# schematicsv2.net
KiCad netlist of a schematic drawn in EAGLE
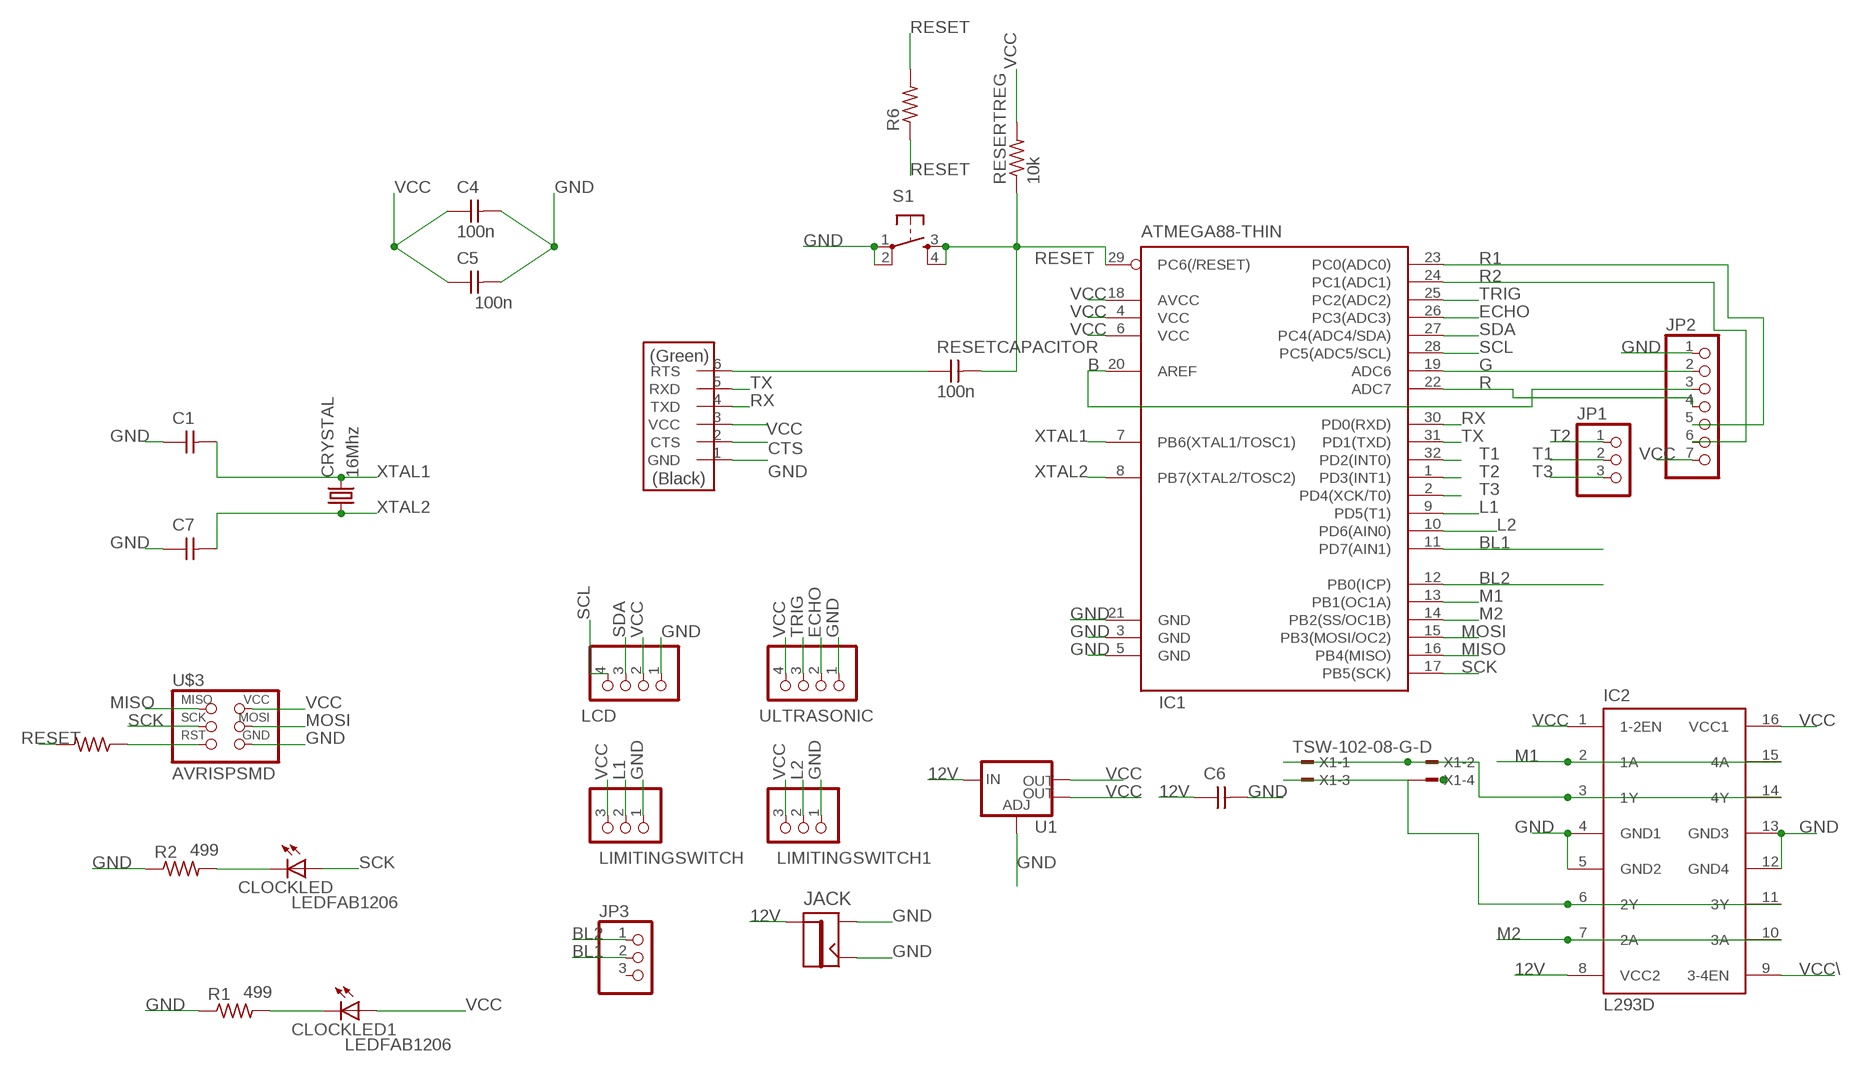
[diagram p0: schematic, sheet 1]

(export (version "E")
  (design (tool "Eeschema 10.0.6"))
  (components
    (comp (ref "C1")
      (value "CAP-UNPOLARIZEDFAB")
      (footprint "eagle-import:C1206FAB")
      (libsource (lib "eagle-import") (part "CAP-UNPOLARIZEDFAB"))
    )
    (comp (ref "C4")
      (value "100n")
      (footprint "eagle-import:C1206FAB")
      (libsource (lib "eagle-import") (part "CAP-UNPOLARIZEDFAB"))
    )
    (comp (ref "C5")
      (value "100n")
      (footprint "eagle-import:C1206FAB")
      (libsource (lib "eagle-import") (part "CAP-UNPOLARIZEDFAB"))
    )
    (comp (ref "C6")
      (value "CAP-UNPOLARIZEDFAB")
      (footprint "eagle-import:C1206FAB")
      (libsource (lib "eagle-import") (part "CAP-UNPOLARIZEDFAB"))
    )
    (comp (ref "C7")
      (value "CAP-UNPOLARIZEDFAB")
      (footprint "eagle-import:C1206FAB")
      (libsource (lib "eagle-import") (part "CAP-UNPOLARIZEDFAB"))
    )
    (comp (ref "CLOCKLED")
      (value "LEDFAB1206")
      (footprint "eagle-import:LED1206FAB")
      (libsource (lib "eagle-import") (part "LEDFAB1206"))
    )
    (comp (ref "CLOCKLED1")
      (value "LEDFAB1206")
      (footprint "eagle-import:LED1206FAB")
      (libsource (lib "eagle-import") (part "LEDFAB1206"))
    )
    (comp (ref "CRYSTAL")
      (value "16Mhz")
      (footprint "eagle-import:CSM-7X-DU")
      (libsource (lib "eagle-import") (part "CSM-7X-DU"))
    )
    (comp (ref "IC1")
      (value "ATMEGA88-THIN")
      (footprint "eagle-import:TQFP32-08THIN")
      (libsource (lib "eagle-import") (part "ATMEGA88-THIN"))
    )
    (comp (ref "IC2")
      (value "L293D")
      (footprint "eagle-import:DIL16")
      (libsource (lib "eagle-import") (part "L293D"))
    )
    (comp (ref "JACK")
      (value "JACK2.1MM")
      (footprint "eagle-import:JACK_2.1MM")
      (libsource (lib "eagle-import") (part "JACK2.1MM"))
    )
    (comp (ref "JP1")
      (value "PINHD-1X31X03_SMT")
      (footprint "eagle-import:1X03_SMT")
      (libsource (lib "eagle-import") (part "PINHD-1X31X03_SMT"))
    )
    (comp (ref "JP2")
      (value "PINHD-1X71X07_SMT")
      (footprint "eagle-import:1X07_SMT")
      (libsource (lib "eagle-import") (part "PINHD-1X71X07_SMT"))
    )
    (comp (ref "JP3")
      (value "PINHD-1X31X03_SMT")
      (footprint "eagle-import:1X03_SMT")
      (libsource (lib "eagle-import") (part "PINHD-1X31X03_SMT"))
    )
    (comp (ref "LCD")
      (value "PINHD-1X41X04_SMT")
      (footprint "eagle-import:1X04_SMT")
      (libsource (lib "eagle-import") (part "PINHD-1X41X04_SMT"))
    )
    (comp (ref "LIMITINGSWITCH")
      (value "PINHD-1X31X03_SMT")
      (footprint "eagle-import:1X03_SMT")
      (libsource (lib "eagle-import") (part "PINHD-1X31X03_SMT"))
    )
    (comp (ref "LIMITINGSWITCH1")
      (value "PINHD-1X31X03_SMT")
      (footprint "eagle-import:1X03_SMT")
      (libsource (lib "eagle-import") (part "PINHD-1X31X03_SMT"))
    )
    (comp (ref "R1")
      (value "499")
      (footprint "eagle-import:R1206FAB")
      (libsource (lib "eagle-import") (part "RES-US1206FAB"))
    )
    (comp (ref "R2")
      (value "499")
      (footprint "eagle-import:R1206FAB")
      (libsource (lib "eagle-import") (part "RES-US1206FAB"))
    )
    (comp (ref "R4")
      (value "1000")
      (footprint "eagle-import:R1206FAB")
      (libsource (lib "eagle-import") (part "RES-US1206FAB"))
    )
    (comp (ref "R6")
      (value "1000")
      (footprint "eagle-import:R1206FAB")
      (libsource (lib "eagle-import") (part "RES-US1206FAB"))
    )
    (comp (ref "RESERTREG")
      (value "10k")
      (footprint "eagle-import:R1206FAB")
      (libsource (lib "eagle-import") (part "RES-US1206FAB"))
    )
    (comp (ref "RESETCAPACITOR")
      (value "100n")
      (footprint "eagle-import:C1206FAB")
      (libsource (lib "eagle-import") (part "CAP-UNPOLARIZEDFAB"))
    )
    (comp (ref "S1")
      (value "6MM_SWITCH6MM_SWITCH")
      (footprint "eagle-import:6MM_SWITCH")
      (libsource (lib "eagle-import") (part "6MM_SWITCH6MM_SWITCH"))
    )
    (comp (ref "U$2")
      (value "FTDI-SMD-HEADER")
      (footprint "eagle-import:1X06SMD")
      (libsource (lib "eagle-import") (part "FTDI-SMD-HEADER"))
    )
    (comp (ref "U$3")
      (value "AVRISPSMD")
      (footprint "eagle-import:2X03SMD")
      (libsource (lib "eagle-import") (part "AVRISPSMD"))
    )
    (comp (ref "U1")
      (value "V_REG_LM1117SOT223")
      (footprint "eagle-import:SOT223")
      (libsource (lib "eagle-import") (part "V_REG_LM1117SOT223"))
    )
    (comp (ref "ULTRASONIC")
      (value "PINHD-1X41X04_SMT")
      (footprint "eagle-import:1X04_SMT")
      (libsource (lib "eagle-import") (part "PINHD-1X41X04_SMT"))
    )
    (comp (ref "X1")
      (value "TSW-102-08-G-D")
      (footprint "eagle-import:TSW-102-XX-G-D")
      (fields (field (name "MF") "Samtec Inc.") (field (name "MPN") "TSW-102-07-G-D"))
      (libsource (lib "eagle-import") (part "TSW-102--G-D08"))
    )
  )
  (nets
    (net (code "1") (name "/12V") (class "Default")
      (node (ref "C6") (pin "1") (pinfunction "1_1") (pintype "passive"))
      (node (ref "IC2") (pin "8") (pinfunction "VCC2_8") (pintype "power_in"))
      (node (ref "JACK") (pin "PIN") (pinfunction "PIN_PIN") (pintype "bidirectional"))
      (node (ref "U1") (pin "3") (pinfunction "IN_3") (pintype "input"))
    )
    (net (code "2") (name "/B") (class "Default")
      (node (ref "IC1") (pin "20") (pinfunction "AREF_20") (pintype "passive"))
      (node (ref "JP2") (pin "3") (pinfunction "3_3") (pintype "passive"))
    )
    (net (code "3") (name "/BL1") (class "Default")
      (node (ref "IC1") (pin "11") (pinfunction "PD7(AIN1)_11") (pintype "bidirectional"))
      (node (ref "JP3") (pin "2") (pinfunction "2_2") (pintype "passive"))
    )
    (net (code "4") (name "/BL2") (class "Default")
      (node (ref "IC1") (pin "12") (pinfunction "PB0(ICP)_12") (pintype "bidirectional"))
      (node (ref "JP3") (pin "1") (pinfunction "1_1") (pintype "passive"))
    )
    (net (code "5") (name "/CTS") (class "Default")
      (node (ref "U$2") (pin "2") (pinfunction "CTS_2") (pintype "bidirectional"))
    )
    (net (code "6") (name "/ECHO") (class "Default")
      (node (ref "IC1") (pin "26") (pinfunction "PC3(ADC3)_26") (pintype "bidirectional"))
      (node (ref "ULTRASONIC") (pin "2") (pinfunction "2_2") (pintype "passive"))
    )
    (net (code "7") (name "/G") (class "Default")
      (node (ref "IC1") (pin "19") (pinfunction "ADC6_19") (pintype "bidirectional"))
      (node (ref "JP2") (pin "2") (pinfunction "2_2") (pintype "passive"))
    )
    (net (code "8") (name "/GND") (class "Default")
      (node (ref "C1") (pin "1") (pinfunction "1_1") (pintype "passive"))
      (node (ref "C4") (pin "2") (pinfunction "2_2") (pintype "passive"))
      (node (ref "C5") (pin "2") (pinfunction "2_2") (pintype "passive"))
      (node (ref "C6") (pin "2") (pinfunction "2_2") (pintype "passive"))
      (node (ref "C7") (pin "1") (pinfunction "1_1") (pintype "passive"))
      (node (ref "IC1") (pin "21") (pinfunction "GND_21") (pintype "power_in"))
      (node (ref "IC1") (pin "3") (pinfunction "GND_3") (pintype "power_in"))
      (node (ref "IC1") (pin "5") (pinfunction "GND_5") (pintype "power_in"))
      (node (ref "IC2") (pin "12") (pinfunction "GND4_12") (pintype "power_in"))
      (node (ref "IC2") (pin "13") (pinfunction "GND3_13") (pintype "power_in"))
      (node (ref "IC2") (pin "4") (pinfunction "GND1_4") (pintype "power_in"))
      (node (ref "IC2") (pin "5") (pinfunction "GND2_5") (pintype "power_in"))
      (node (ref "JACK") (pin "CONTACT") (pinfunction "CONTACT_CONTACT") (pintype "bidirectional"))
      (node (ref "JACK") (pin "SHUNT") (pinfunction "SHUNT_SHUNT") (pintype "bidirectional"))
      (node (ref "JP2") (pin "1") (pinfunction "1_1") (pintype "passive"))
      (node (ref "LCD") (pin "1") (pinfunction "1_1") (pintype "passive"))
      (node (ref "LIMITINGSWITCH") (pin "1") (pinfunction "1_1") (pintype "passive"))
      (node (ref "LIMITINGSWITCH1") (pin "1") (pinfunction "1_1") (pintype "passive"))
      (node (ref "R1") (pin "1") (pinfunction "1_1") (pintype "passive"))
      (node (ref "R2") (pin "1") (pinfunction "1_1") (pintype "passive"))
      (node (ref "S1") (pin "1") (pinfunction "P_1") (pintype "passive"))
      (node (ref "S1") (pin "2") (pinfunction "P1_2") (pintype "passive"))
      (node (ref "U$2") (pin "1") (pinfunction "GND_1") (pintype "bidirectional"))
      (node (ref "U$3") (pin "6") (pinfunction "GND_6") (pintype "passive"))
      (node (ref "U1") (pin "1") (pinfunction "ADJ_1") (pintype "input"))
      (node (ref "ULTRASONIC") (pin "1") (pinfunction "1_1") (pintype "passive"))
    )
    (net (code "9") (name "/L1") (class "Default")
      (node (ref "IC1") (pin "9") (pinfunction "PD5(T1)_9") (pintype "bidirectional"))
      (node (ref "LIMITINGSWITCH") (pin "2") (pinfunction "2_2") (pintype "passive"))
    )
    (net (code "10") (name "/L2") (class "Default")
      (node (ref "IC1") (pin "10") (pinfunction "PD6(AIN0)_10") (pintype "bidirectional"))
      (node (ref "LIMITINGSWITCH1") (pin "2") (pinfunction "2_2") (pintype "passive"))
    )
    (net (code "11") (name "/M1") (class "Default")
      (node (ref "IC1") (pin "13") (pinfunction "PB1(OC1A)_13") (pintype "bidirectional"))
      (node (ref "IC2") (pin "15") (pinfunction "4A_15") (pintype "input"))
      (node (ref "IC2") (pin "2") (pinfunction "1A_2") (pintype "input"))
    )
    (net (code "12") (name "/M2") (class "Default")
      (node (ref "IC1") (pin "14") (pinfunction "PB2(SS/OC1B)_14") (pintype "bidirectional"))
      (node (ref "IC2") (pin "10") (pinfunction "3A_10") (pintype "input"))
      (node (ref "IC2") (pin "7") (pinfunction "2A_7") (pintype "input"))
    )
    (net (code "13") (name "/MISO") (class "Default")
      (node (ref "IC1") (pin "16") (pinfunction "PB4(MISO)_16") (pintype "bidirectional"))
      (node (ref "U$3") (pin "1") (pinfunction "MISO_1") (pintype "passive"))
    )
    (net (code "14") (name "/MOSI") (class "Default")
      (node (ref "IC1") (pin "15") (pinfunction "PB3(MOSI/OC2)_15") (pintype "bidirectional"))
      (node (ref "U$3") (pin "4") (pinfunction "MOSI_4") (pintype "passive"))
    )
    (net (code "15") (name "/R") (class "Default")
      (node (ref "IC1") (pin "22") (pinfunction "ADC7_22") (pintype "bidirectional"))
      (node (ref "JP2") (pin "4") (pinfunction "4_4") (pintype "passive"))
    )
    (net (code "16") (name "/R1") (class "Default")
      (node (ref "IC1") (pin "23") (pinfunction "PC0(ADC0)_23") (pintype "bidirectional"))
      (node (ref "JP2") (pin "5") (pinfunction "5_5") (pintype "passive"))
    )
    (net (code "17") (name "/R2") (class "Default")
      (node (ref "IC1") (pin "24") (pinfunction "PC1(ADC1)_24") (pintype "bidirectional"))
      (node (ref "JP2") (pin "6") (pinfunction "6_6") (pintype "passive"))
    )
    (net (code "18") (name "/RESET") (class "Default")
      (node (ref "IC1") (pin "29") (pinfunction "PC6(/RESET)_29") (pintype "bidirectional"))
      (node (ref "R4") (pin "2") (pinfunction "2_2") (pintype "passive"))
      (node (ref "R6") (pin "1") (pinfunction "1_1") (pintype "passive"))
      (node (ref "R6") (pin "2") (pinfunction "2_2") (pintype "passive"))
      (node (ref "RESERTREG") (pin "1") (pinfunction "1_1") (pintype "passive"))
      (node (ref "RESETCAPACITOR") (pin "2") (pinfunction "2_2") (pintype "passive"))
      (node (ref "S1") (pin "3") (pinfunction "S_3") (pintype "passive"))
      (node (ref "S1") (pin "4") (pinfunction "S1_4") (pintype "passive"))
    )
    (net (code "19") (name "/RX") (class "Default")
      (node (ref "IC1") (pin "30") (pinfunction "PD0(RXD)_30") (pintype "bidirectional"))
      (node (ref "U$2") (pin "4") (pinfunction "TXD_4") (pintype "bidirectional"))
    )
    (net (code "20") (name "/SCK") (class "Default")
      (node (ref "CLOCKLED") (pin "1") (pinfunction "A_1") (pintype "passive"))
      (node (ref "IC1") (pin "17") (pinfunction "PB5(SCK)_17") (pintype "bidirectional"))
      (node (ref "U$3") (pin "3") (pinfunction "SCK_3") (pintype "passive"))
    )
    (net (code "21") (name "/SCL") (class "Default")
      (node (ref "IC1") (pin "28") (pinfunction "PC5(ADC5/SCL)_28") (pintype "bidirectional"))
      (node (ref "LCD") (pin "4") (pinfunction "4_4") (pintype "passive"))
    )
    (net (code "22") (name "/SDA") (class "Default")
      (node (ref "IC1") (pin "27") (pinfunction "PC4(ADC4/SDA)_27") (pintype "bidirectional"))
      (node (ref "LCD") (pin "3") (pinfunction "3_3") (pintype "passive"))
    )
    (net (code "23") (name "/T1") (class "Default")
      (node (ref "IC1") (pin "32") (pinfunction "PD2(INT0)_32") (pintype "bidirectional"))
      (node (ref "JP1") (pin "2") (pinfunction "2_2") (pintype "passive"))
    )
    (net (code "24") (name "/T2") (class "Default")
      (node (ref "IC1") (pin "1") (pinfunction "PD3(INT1)_1") (pintype "bidirectional"))
      (node (ref "JP1") (pin "1") (pinfunction "1_1") (pintype "passive"))
    )
    (net (code "25") (name "/T3") (class "Default")
      (node (ref "IC1") (pin "2") (pinfunction "PD4(XCK/T0)_2") (pintype "bidirectional"))
      (node (ref "JP1") (pin "3") (pinfunction "3_3") (pintype "passive"))
    )
    (net (code "26") (name "/TRIG") (class "Default")
      (node (ref "IC1") (pin "25") (pinfunction "PC2(ADC2)_25") (pintype "bidirectional"))
      (node (ref "ULTRASONIC") (pin "3") (pinfunction "3_3") (pintype "passive"))
    )
    (net (code "27") (name "/TX") (class "Default")
      (node (ref "IC1") (pin "31") (pinfunction "PD1(TXD)_31") (pintype "bidirectional"))
      (node (ref "U$2") (pin "5") (pinfunction "RXD_5") (pintype "bidirectional"))
    )
    (net (code "28") (name "/VCC") (class "Default")
      (node (ref "C4") (pin "1") (pinfunction "1_1") (pintype "passive"))
      (node (ref "C5") (pin "1") (pinfunction "1_1") (pintype "passive"))
      (node (ref "CLOCKLED1") (pin "1") (pinfunction "A_1") (pintype "passive"))
      (node (ref "IC1") (pin "18") (pinfunction "AVCC_18") (pintype "power_in"))
      (node (ref "IC1") (pin "4") (pinfunction "VCC_4") (pintype "power_in"))
      (node (ref "IC1") (pin "6") (pinfunction "VCC_6") (pintype "power_in"))
      (node (ref "IC2") (pin "1") (pinfunction "1-2EN_1") (pintype "input"))
      (node (ref "IC2") (pin "16") (pinfunction "VCC1_16") (pintype "power_in"))
      (node (ref "JP2") (pin "7") (pinfunction "7_7") (pintype "passive"))
      (node (ref "LCD") (pin "2") (pinfunction "2_2") (pintype "passive"))
      (node (ref "LIMITINGSWITCH") (pin "3") (pinfunction "3_3") (pintype "passive"))
      (node (ref "LIMITINGSWITCH1") (pin "3") (pinfunction "3_3") (pintype "passive"))
      (node (ref "RESERTREG") (pin "2") (pinfunction "2_2") (pintype "passive"))
      (node (ref "U$2") (pin "3") (pinfunction "VCC_3") (pintype "bidirectional"))
      (node (ref "U$3") (pin "2") (pinfunction "VCC_2") (pintype "passive"))
      (node (ref "U1") (pin "2") (pinfunction "OUT_2") (pintype "output"))
      (node (ref "U1") (pin "4") (pinfunction "OUT_4") (pintype "output"))
      (node (ref "ULTRASONIC") (pin "4") (pinfunction "4_4") (pintype "passive"))
    )
    (net (code "29") (name "/VCC\\") (class "Default")
      (node (ref "IC2") (pin "9") (pinfunction "3-4EN_9") (pintype "input"))
    )
    (net (code "30") (name "/XTAL1") (class "Default")
      (node (ref "C1") (pin "2") (pinfunction "2_2") (pintype "passive"))
      (node (ref "CRYSTAL") (pin "2") (pinfunction "2_2") (pintype "passive"))
      (node (ref "IC1") (pin "7") (pinfunction "PB6(XTAL1/TOSC1)_7") (pintype "bidirectional"))
    )
    (net (code "31") (name "/XTAL2") (class "Default")
      (node (ref "C7") (pin "2") (pinfunction "2_2") (pintype "passive"))
      (node (ref "CRYSTAL") (pin "1") (pinfunction "1_1") (pintype "passive"))
      (node (ref "IC1") (pin "8") (pinfunction "PB7(XTAL2/TOSC2)_8") (pintype "bidirectional"))
    )
    (net (code "32") (name "Net-(CLOCKLED-C)") (class "Default")
      (node (ref "CLOCKLED") (pin "2") (pinfunction "C_2") (pintype "passive"))
      (node (ref "R2") (pin "2") (pinfunction "2_2") (pintype "passive"))
    )
    (net (code "33") (name "Net-(CLOCKLED1-C)") (class "Default")
      (node (ref "CLOCKLED1") (pin "2") (pinfunction "C_2") (pintype "passive"))
      (node (ref "R1") (pin "2") (pinfunction "2_2") (pintype "passive"))
    )
    (net (code "34") (name "Net-(IC2-1Y)") (class "Default")
      (node (ref "IC2") (pin "14") (pinfunction "4Y_14") (pintype "output"))
      (node (ref "IC2") (pin "3") (pinfunction "1Y_3") (pintype "output"))
      (node (ref "X1") (pin "1") (pinfunction "1_1") (pintype "passive"))
      (node (ref "X1") (pin "2") (pinfunction "1_2") (pintype "passive"))
    )
    (net (code "35") (name "Net-(IC2-2Y)") (class "Default")
      (node (ref "IC2") (pin "11") (pinfunction "3Y_11") (pintype "output"))
      (node (ref "IC2") (pin "6") (pinfunction "2Y_6") (pintype "output"))
      (node (ref "X1") (pin "3") (pinfunction "1_3") (pintype "passive"))
      (node (ref "X1") (pin "4") (pinfunction "1_4") (pintype "passive"))
    )
    (net (code "36") (name "Net-(U$2-RTS)") (class "Default")
      (node (ref "RESETCAPACITOR") (pin "1") (pinfunction "1_1") (pintype "passive"))
      (node (ref "U$2") (pin "6") (pinfunction "RTS_6") (pintype "bidirectional"))
    )
    (net (code "37") (name "Net-(U$3-RST)") (class "Default")
      (node (ref "R4") (pin "1") (pinfunction "1_1") (pintype "passive"))
      (node (ref "U$3") (pin "5") (pinfunction "RST_5") (pintype "passive"))
    )
    (net (code "38") (name "unconnected-(JP3-Pad3)") (class "Default")
      (node (ref "JP3") (pin "3") (pinfunction "3_3") (pintype "passive"))
    )
  )
)
